# FillSensor.net
KiCad netlist of a schematic drawn in EAGLE
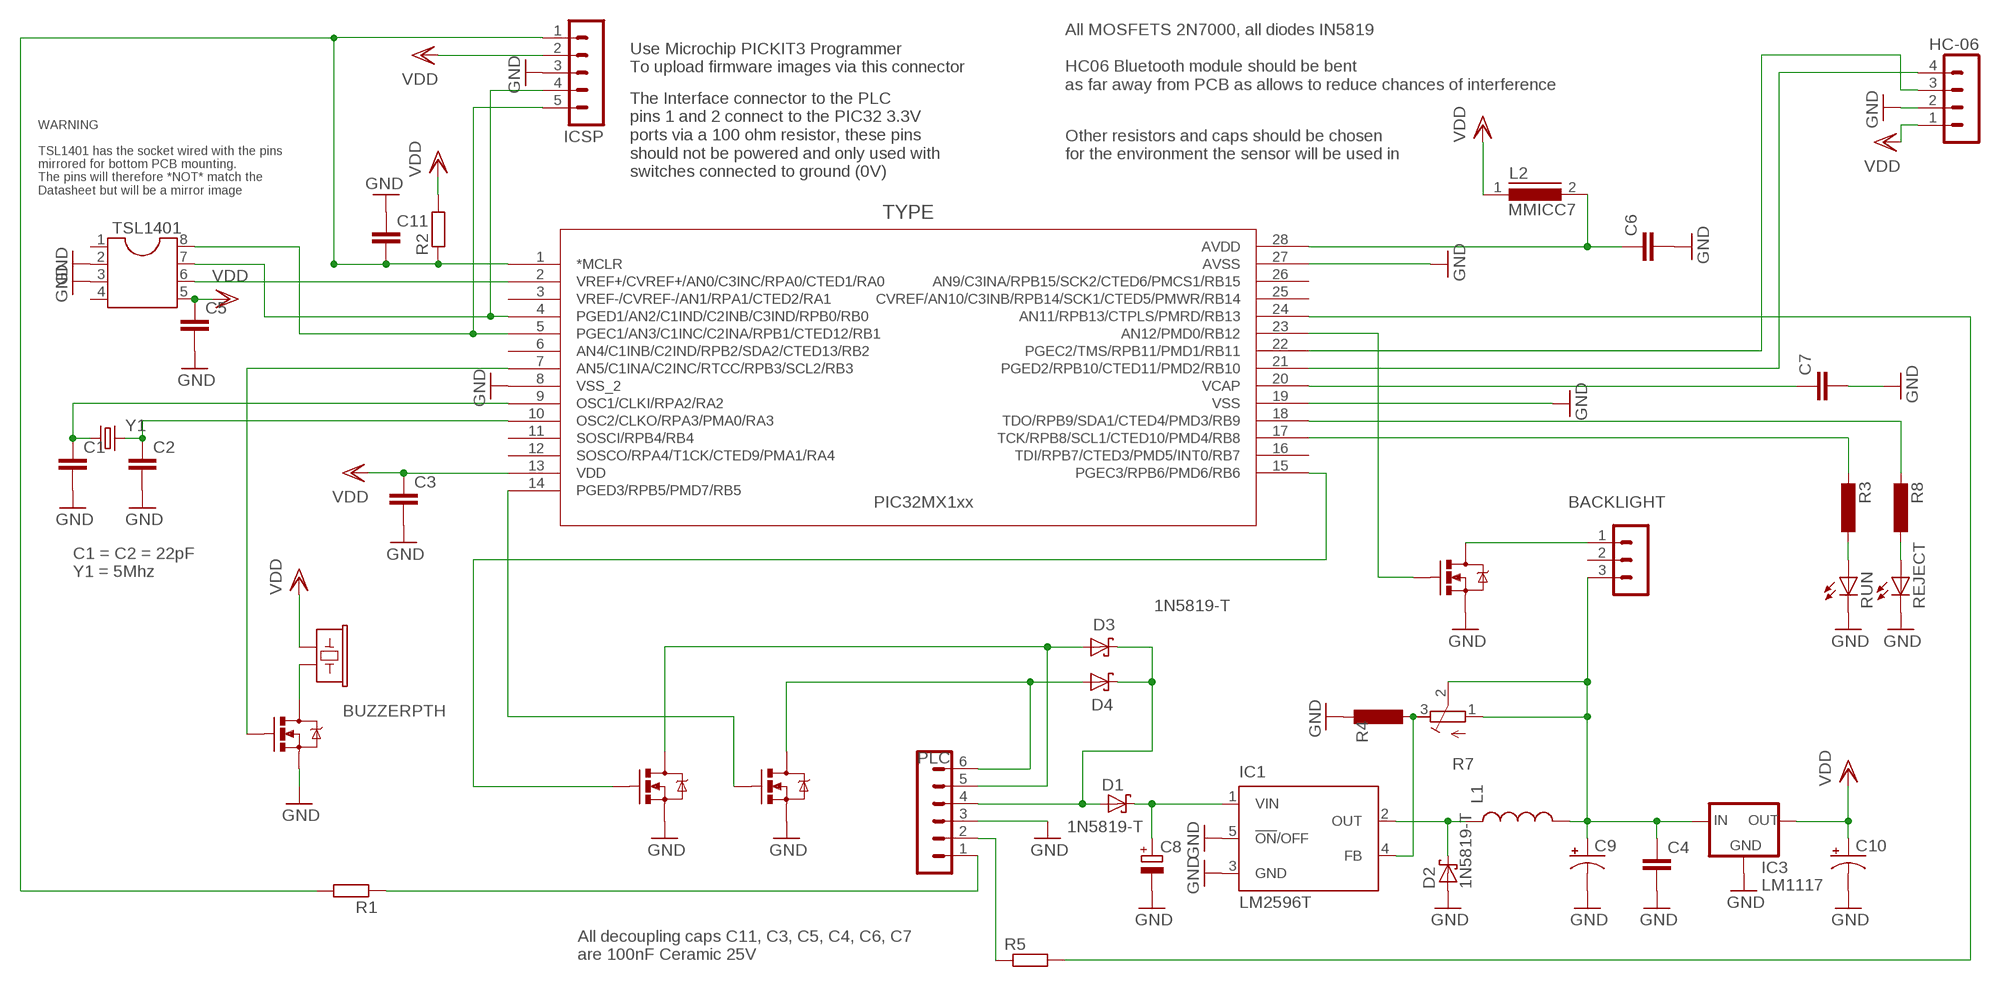
[diagram p0: schematic, sheet 1]

(export (version "E")
  (design (tool "Eeschema 10.0.6"))
  (components
    (comp (ref "BACKLIGHT")
      (value "MA03-1")
      (footprint "eagle-import:MA03-1")
      (libsource (lib "eagle-import") (part "MA03-1"))
    )
    (comp (ref "C1")
      (value "CAPPTH")
      (footprint "eagle-import:CAP-PTH-SMALL")
      (libsource (lib "eagle-import") (part "CAPPTH"))
    )
    (comp (ref "C2")
      (value "CAPPTH")
      (footprint "eagle-import:CAP-PTH-SMALL")
      (libsource (lib "eagle-import") (part "CAPPTH"))
    )
    (comp (ref "C3")
      (value "CAPPTH")
      (footprint "eagle-import:CAP-PTH-SMALL")
      (libsource (lib "eagle-import") (part "CAPPTH"))
    )
    (comp (ref "C4")
      (value "CAPPTH")
      (footprint "eagle-import:CAP-PTH-SMALL")
      (libsource (lib "eagle-import") (part "CAPPTH"))
    )
    (comp (ref "C5")
      (value "CAPPTH")
      (footprint "eagle-import:CAP-PTH-SMALL")
      (libsource (lib "eagle-import") (part "CAPPTH"))
    )
    (comp (ref "C6")
      (value "CAPPTH")
      (footprint "eagle-import:CAP-PTH-SMALL")
      (libsource (lib "eagle-import") (part "CAPPTH"))
    )
    (comp (ref "C7")
      (value "CAPPTH")
      (footprint "eagle-import:CAP-PTH-SMALL")
      (libsource (lib "eagle-import") (part "CAPPTH"))
    )
    (comp (ref "C8")
      (value "CPOL-EUE5-5")
      (footprint "eagle-import:E5-5")
      (libsource (lib "eagle-import") (part "CPOL-EUE5-5"))
    )
    (comp (ref "C9")
      (value "CAP_POLPTH2")
      (footprint "eagle-import:CPOL-RADIAL-10UF-25V")
      (libsource (lib "eagle-import") (part "CAP_POLPTH2"))
    )
    (comp (ref "C10")
      (value "CAP_POLPTH2")
      (footprint "eagle-import:CPOL-RADIAL-10UF-25V")
      (libsource (lib "eagle-import") (part "CAP_POLPTH2"))
    )
    (comp (ref "C11")
      (value "CAPPTH")
      (footprint "eagle-import:CAP-PTH-SMALL")
      (libsource (lib "eagle-import") (part "CAPPTH"))
    )
    (comp (ref "D1")
      (value "1N5819-T")
      (footprint "eagle-import:DO41-7.6")
      (libsource (lib "eagle-import") (part "1N5819-T"))
    )
    (comp (ref "D2")
      (value "1N5819-T")
      (footprint "eagle-import:DO41-7.6")
      (libsource (lib "eagle-import") (part "1N5819-T"))
    )
    (comp (ref "D3")
      (value "1N5819-T")
      (footprint "eagle-import:DO41-7.6")
      (libsource (lib "eagle-import") (part "1N5819-T"))
    )
    (comp (ref "D4")
      (value "1N5819-T")
      (footprint "eagle-import:DO41-7.6")
      (libsource (lib "eagle-import") (part "1N5819-T"))
    )
    (comp (ref "HC-06")
      (value "MA04-1")
      (footprint "eagle-import:MA04-1")
      (libsource (lib "eagle-import") (part "MA04-1"))
    )
    (comp (ref "IC1")
      (value "LM2596T")
      (footprint "eagle-import:T05D")
      (fields
        (field (name "MPN") "LM2596T-ADJ/LF02")
        (field (name "MPN_1") "LM2596T-ADJ/LF02")
        (field (name "OC_FARNELL") "9494162")
        (field (name "OC_NEWARK") "65K5910")
      )
      (libsource (lib "eagle-import") (part "LM2596T"))
    )
    (comp (ref "IC3")
      (value "LM1117")
      (footprint "eagle-import:TO252")
      (libsource (lib "eagle-import") (part "LM1117DTX-3.3"))
    )
    (comp (ref "ICSP")
      (value "MA05-1")
      (footprint "eagle-import:MA05-1")
      (libsource (lib "eagle-import") (part "MA05-1"))
    )
    (comp (ref "L1")
      (value "INDUCTORPWR")
      (footprint "eagle-import:CDRH125")
      (libsource (lib "eagle-import") (part "INDUCTORPWR"))
    )
    (comp (ref "L2")
      (value "MMICC7")
      (footprint "eagle-import:MMICC7")
      (libsource (lib "eagle-import") (part "MMICC7"))
    )
    (comp (ref "PLC")
      (value "MA06-1")
      (footprint "eagle-import:MA06-1")
      (libsource (lib "eagle-import") (part "MA06-1"))
    )
    (comp (ref "Q1")
      (value "MOSFET-NCHANNEL2N7000")
      (footprint "eagle-import:TO-92-AMMO")
      (libsource (lib "eagle-import") (part "MOSFET-NCHANNEL2N7000"))
    )
    (comp (ref "Q2")
      (value "MOSFET-NCHANNEL2N7000")
      (footprint "eagle-import:TO-92-AMMO")
      (libsource (lib "eagle-import") (part "MOSFET-NCHANNEL2N7000"))
    )
    (comp (ref "Q3")
      (value "MOSFET-NCHANNEL2N7000")
      (footprint "eagle-import:TO-92-AMMO")
      (libsource (lib "eagle-import") (part "MOSFET-NCHANNEL2N7000"))
    )
    (comp (ref "Q4")
      (value "MOSFET-NCHANNEL2N7000")
      (footprint "eagle-import:TO-92-AMMO")
      (libsource (lib "eagle-import") (part "MOSFET-NCHANNEL2N7000"))
    )
    (comp (ref "R1")
      (value "R-EU_0207/10")
      (footprint "eagle-import:0207_10")
      (libsource (lib "eagle-import") (part "R-EU_0207/10"))
    )
    (comp (ref "R2")
      (value "R-EU_0207/10")
      (footprint "eagle-import:0207_10")
      (libsource (lib "eagle-import") (part "R-EU_0207/10"))
    )
    (comp (ref "R3")
      (value "L-EU0207/10")
      (footprint "eagle-import:0207_10")
      (libsource (lib "eagle-import") (part "L-EU0207/10"))
    )
    (comp (ref "R4")
      (value "L-EU0207/10")
      (footprint "eagle-import:0207_10")
      (libsource (lib "eagle-import") (part "L-EU0207/10"))
    )
    (comp (ref "R5")
      (value "R-EU_0207/10")
      (footprint "eagle-import:0207_10")
      (libsource (lib "eagle-import") (part "R-EU_0207/10"))
    )
    (comp (ref "R7")
      (value "R-TRIMM64W")
      (footprint "eagle-import:RTRIM64W")
      (libsource (lib "eagle-import") (part "R-TRIMM64W"))
    )
    (comp (ref "R8")
      (value "L-EU0207/10")
      (footprint "eagle-import:0207_10")
      (libsource (lib "eagle-import") (part "L-EU0207/10"))
    )
    (comp (ref "REJECT")
      (value "LED5MM")
      (footprint "eagle-import:LED5MM")
      (libsource (lib "eagle-import") (part "LED5MM"))
    )
    (comp (ref "RUN")
      (value "LED5MM")
      (footprint "eagle-import:LED5MM")
      (libsource (lib "eagle-import") (part "LED5MM"))
    )
    (comp (ref "SG1")
      (value "BUZZERPTH")
      (footprint "eagle-import:BUZZER-12MM")
      (libsource (lib "eagle-import") (part "BUZZERPTH"))
    )
    (comp (ref "TSL1401")
      (value "DIL8")
      (footprint "eagle-import:DIL08")
      (libsource (lib "eagle-import") (part "DIL8"))
    )
    (comp (ref "U1")
      (value "PIC32MX150F128B-")
      (footprint "eagle-import:SPDIP28_300MC")
      (libsource (lib "eagle-import") (part "PIC32MX150F128B-"))
    )
    (comp (ref "Y1")
      (value "CRYSTALHC49UV")
      (footprint "eagle-import:HC49U-V")
      (libsource (lib "eagle-import") (part "CRYSTALHC49UV"))
    )
  )
  (nets
    (net (code "1") (name "GND") (class "Default")
      (node (ref "C1") (pin "2") (pinfunction "2_2") (pintype "passive"))
      (node (ref "C10") (pin "2") (pinfunction "-_2") (pintype "passive"))
      (node (ref "C11") (pin "1") (pinfunction "1_1") (pintype "passive"))
      (node (ref "C2") (pin "2") (pinfunction "2_2") (pintype "passive"))
      (node (ref "C3") (pin "2") (pinfunction "2_2") (pintype "passive"))
      (node (ref "C4") (pin "2") (pinfunction "2_2") (pintype "passive"))
      (node (ref "C5") (pin "2") (pinfunction "2_2") (pintype "passive"))
      (node (ref "C6") (pin "2") (pinfunction "2_2") (pintype "passive"))
      (node (ref "C7") (pin "2") (pinfunction "2_2") (pintype "passive"))
      (node (ref "C8") (pin "-") (pinfunction "-_-") (pintype "passive"))
      (node (ref "C9") (pin "2") (pinfunction "-_2") (pintype "passive"))
      (node (ref "D2") (pin "A") (pinfunction "A_A") (pintype "passive"))
      (node (ref "HC-06") (pin "2") (pinfunction "2_2") (pintype "passive"))
      (node (ref "IC1") (pin "3") (pinfunction "GND_3") (pintype "power_in"))
      (node (ref "IC1") (pin "5") (pinfunction "~{ON}/OFF_5") (pintype "input"))
      (node (ref "IC3") (pin "1") (pinfunction "GND_1") (pintype "input"))
      (node (ref "ICSP") (pin "3") (pinfunction "3_3") (pintype "passive"))
      (node (ref "PLC") (pin "3") (pinfunction "3_3") (pintype "passive"))
      (node (ref "Q1") (pin "1") (pinfunction "S_1") (pintype "passive"))
      (node (ref "Q2") (pin "1") (pinfunction "S_1") (pintype "passive"))
      (node (ref "Q3") (pin "1") (pinfunction "S_1") (pintype "passive"))
      (node (ref "Q4") (pin "1") (pinfunction "S_1") (pintype "passive"))
      (node (ref "R4") (pin "1") (pinfunction "1_1") (pintype "passive"))
      (node (ref "REJECT") (pin "K") (pinfunction "C_K") (pintype "passive"))
      (node (ref "RUN") (pin "K") (pinfunction "C_K") (pintype "passive"))
      (node (ref "TSL1401") (pin "2") (pinfunction "2_2") (pintype "passive"))
      (node (ref "TSL1401") (pin "3") (pinfunction "3_3") (pintype "passive"))
      (node (ref "U1") (pin "19") (pinfunction "VSS_19") (pintype "passive"))
      (node (ref "U1") (pin "27") (pinfunction "AVSS_27") (pintype "passive"))
      (node (ref "U1") (pin "8") (pinfunction "VSS_2_8") (pintype "passive"))
    )
    (net (code "2") (name "Net-(C9-+)") (class "Default")
      (node (ref "BACKLIGHT") (pin "3") (pinfunction "3_3") (pintype "passive"))
      (node (ref "C4") (pin "1") (pinfunction "1_1") (pintype "passive"))
      (node (ref "C9") (pin "1") (pinfunction "+_1") (pintype "passive"))
      (node (ref "IC3") (pin "2") (pinfunction "IN_2") (pintype "input"))
      (node (ref "L1") (pin "2") (pinfunction "2_2") (pintype "passive"))
      (node (ref "R7") (pin "1") (pinfunction "E_1") (pintype "passive"))
      (node (ref "R7") (pin "2") (pinfunction "S_2") (pintype "passive"))
    )
    (net (code "3") (name "Net-(D1-PadA)") (class "Default")
      (node (ref "D1") (pin "A") (pinfunction "A_A") (pintype "passive"))
      (node (ref "D3") (pin "C") (pinfunction "C_C") (pintype "passive"))
      (node (ref "D4") (pin "C") (pinfunction "C_C") (pintype "passive"))
      (node (ref "PLC") (pin "4") (pinfunction "4_4") (pintype "passive"))
    )
    (net (code "4") (name "Net-(IC1-FB)") (class "Default")
      (node (ref "IC1") (pin "4") (pinfunction "FB_4") (pintype "input"))
      (node (ref "R4") (pin "2") (pinfunction "2_2") (pintype "passive"))
      (node (ref "R7") (pin "3") (pinfunction "A_3") (pintype "passive"))
    )
    (net (code "5") (name "Net-(IC1-OUT)") (class "Default")
      (node (ref "D2") (pin "C") (pinfunction "C_C") (pintype "passive"))
      (node (ref "IC1") (pin "2") (pinfunction "OUT_2") (pintype "output"))
      (node (ref "L1") (pin "1") (pinfunction "1_1") (pintype "passive"))
    )
    (net (code "6") (name "Net-(IC1-VIN)") (class "Default")
      (node (ref "C8") (pin "+") (pinfunction "+_+") (pintype "passive"))
      (node (ref "D1") (pin "C") (pinfunction "C_C") (pintype "passive"))
      (node (ref "IC1") (pin "1") (pinfunction "VIN_1") (pintype "input"))
    )
    (net (code "7") (name "Net-(PLC-Pad1)") (class "Default")
      (node (ref "PLC") (pin "1") (pinfunction "1_1") (pintype "passive"))
      (node (ref "R1") (pin "1") (pinfunction "1_1") (pintype "passive"))
    )
    (net (code "8") (name "Net-(PLC-Pad2)") (class "Default")
      (node (ref "PLC") (pin "2") (pinfunction "2_2") (pintype "passive"))
      (node (ref "R5") (pin "1") (pinfunction "1_1") (pintype "passive"))
    )
    (net (code "9") (name "Net-(Q1-D)") (class "Default")
      (node (ref "D4") (pin "A") (pinfunction "A_A") (pintype "passive"))
      (node (ref "PLC") (pin "6") (pinfunction "6_6") (pintype "passive"))
      (node (ref "Q1") (pin "3") (pinfunction "D_3") (pintype "passive"))
    )
    (net (code "10") (name "Net-(Q1-G)") (class "Default")
      (node (ref "Q1") (pin "2") (pinfunction "G_2") (pintype "passive"))
      (node (ref "U1") (pin "14") (pinfunction "PGED3/RPB5/PMD7/RB5_14") (pintype "passive"))
    )
    (net (code "11") (name "Net-(Q2-D)") (class "Default")
      (node (ref "D3") (pin "A") (pinfunction "A_A") (pintype "passive"))
      (node (ref "PLC") (pin "5") (pinfunction "5_5") (pintype "passive"))
      (node (ref "Q2") (pin "3") (pinfunction "D_3") (pintype "passive"))
    )
    (net (code "12") (name "Net-(Q2-G)") (class "Default")
      (node (ref "Q2") (pin "2") (pinfunction "G_2") (pintype "passive"))
      (node (ref "U1") (pin "15") (pinfunction "PGEC3/RPB6/PMD6/RB6_15") (pintype "passive"))
    )
    (net (code "13") (name "Net-(Q3-D)") (class "Default")
      (node (ref "BACKLIGHT") (pin "1") (pinfunction "1_1") (pintype "passive"))
      (node (ref "Q3") (pin "3") (pinfunction "D_3") (pintype "passive"))
    )
    (net (code "14") (name "Net-(Q3-G)") (class "Default")
      (node (ref "Q3") (pin "2") (pinfunction "G_2") (pintype "passive"))
      (node (ref "U1") (pin "23") (pinfunction "AN12/PMD0/RB12_23") (pintype "passive"))
    )
    (net (code "15") (name "Net-(Q4-D)") (class "Default")
      (node (ref "Q4") (pin "3") (pinfunction "D_3") (pintype "passive"))
      (node (ref "SG1") (pin "-") (pinfunction "2_-") (pintype "passive"))
    )
    (net (code "16") (name "Net-(Q4-G)") (class "Default")
      (node (ref "Q4") (pin "2") (pinfunction "G_2") (pintype "passive"))
      (node (ref "U1") (pin "7") (pinfunction "AN5/C1INA/C2INC/RTCC/RPB3/SCL2/RB3_7") (pintype "passive"))
    )
    (net (code "17") (name "Net-(R3-Pad1)") (class "Default")
      (node (ref "R3") (pin "1") (pinfunction "1_1") (pintype "passive"))
      (node (ref "RUN") (pin "A") (pinfunction "A_A") (pintype "passive"))
    )
    (net (code "18") (name "Net-(R8-Pad1)") (class "Default")
      (node (ref "R8") (pin "1") (pinfunction "1_1") (pintype "passive"))
      (node (ref "REJECT") (pin "A") (pinfunction "A_A") (pintype "passive"))
    )
    (net (code "19") (name "Net-(U1-*MCLR)") (class "Default")
      (node (ref "C11") (pin "2") (pinfunction "2_2") (pintype "passive"))
      (node (ref "ICSP") (pin "1") (pinfunction "1_1") (pintype "passive"))
      (node (ref "R1") (pin "2") (pinfunction "2_2") (pintype "passive"))
      (node (ref "R2") (pin "1") (pinfunction "1_1") (pintype "passive"))
      (node (ref "U1") (pin "1") (pinfunction "*MCLR_1") (pintype "passive"))
    )
    (net (code "20") (name "Net-(U1-AN11{slash}RPB13{slash}CTPLS{slash}PMRD{slash}RB13)") (class "Default")
      (node (ref "R5") (pin "2") (pinfunction "2_2") (pintype "passive"))
      (node (ref "U1") (pin "24") (pinfunction "AN11/RPB13/CTPLS/PMRD/RB13_24") (pintype "passive"))
    )
    (net (code "21") (name "Net-(U1-AVDD)") (class "Default")
      (node (ref "C6") (pin "1") (pinfunction "1_1") (pintype "passive"))
      (node (ref "L2") (pin "2") (pinfunction "2_2") (pintype "passive"))
      (node (ref "U1") (pin "28") (pinfunction "AVDD_28") (pintype "passive"))
    )
    (net (code "22") (name "Net-(U1-OSC1{slash}CLKI{slash}RPA2{slash}RA2)") (class "Default")
      (node (ref "C1") (pin "1") (pinfunction "1_1") (pintype "passive"))
      (node (ref "U1") (pin "9") (pinfunction "OSC1/CLKI/RPA2/RA2_9") (pintype "passive"))
      (node (ref "Y1") (pin "1") (pinfunction "1_1") (pintype "passive"))
    )
    (net (code "23") (name "Net-(U1-OSC2{slash}CLKO{slash}RPA3{slash}PMA0{slash}RA3)") (class "Default")
      (node (ref "C2") (pin "1") (pinfunction "1_1") (pintype "passive"))
      (node (ref "U1") (pin "10") (pinfunction "OSC2/CLKO/RPA3/PMA0/RA3_10") (pintype "passive"))
      (node (ref "Y1") (pin "2") (pinfunction "2_2") (pintype "passive"))
    )
    (net (code "24") (name "Net-(U1-PGEC1{slash}AN3{slash}C1INC{slash}C2INA{slash}RPB1{slash}CTED12{slash}RB1)") (class "Default")
      (node (ref "ICSP") (pin "5") (pinfunction "5_5") (pintype "passive"))
      (node (ref "TSL1401") (pin "8") (pinfunction "8_8") (pintype "passive"))
      (node (ref "U1") (pin "5") (pinfunction "PGEC1/AN3/C1INC/C2INA/RPB1/CTED12/RB1_5") (pintype "passive"))
    )
    (net (code "25") (name "Net-(U1-PGEC2{slash}TMS{slash}RPB11{slash}PMD1{slash}RB11)") (class "Default")
      (node (ref "HC-06") (pin "3") (pinfunction "3_3") (pintype "passive"))
      (node (ref "U1") (pin "22") (pinfunction "PGEC2/TMS/RPB11/PMD1/RB11_22") (pintype "passive"))
    )
    (net (code "26") (name "Net-(U1-PGED1{slash}AN2{slash}C1IND{slash}C2INB{slash}C3IND{slash}RPB0{slash}RB0)") (class "Default")
      (node (ref "ICSP") (pin "4") (pinfunction "4_4") (pintype "passive"))
      (node (ref "TSL1401") (pin "7") (pinfunction "7_7") (pintype "passive"))
      (node (ref "U1") (pin "4") (pinfunction "PGED1/AN2/C1IND/C2INB/C3IND/RPB0/RB0_4") (pintype "passive"))
    )
    (net (code "27") (name "Net-(U1-PGED2{slash}RPB10{slash}CTED11{slash}PMD2{slash}RB10)") (class "Default")
      (node (ref "HC-06") (pin "4") (pinfunction "4_4") (pintype "passive"))
      (node (ref "U1") (pin "21") (pinfunction "PGED2/RPB10/CTED11/PMD2/RB10_21") (pintype "passive"))
    )
    (net (code "28") (name "Net-(U1-TCK{slash}RPB8{slash}SCL1{slash}CTED10{slash}PMD4{slash}RB8)") (class "Default")
      (node (ref "R3") (pin "2") (pinfunction "2_2") (pintype "passive"))
      (node (ref "U1") (pin "17") (pinfunction "TCK/RPB8/SCL1/CTED10/PMD4/RB8_17") (pintype "passive"))
    )
    (net (code "29") (name "Net-(U1-TDO{slash}RPB9{slash}SDA1{slash}CTED4{slash}PMD3{slash}RB9)") (class "Default")
      (node (ref "R8") (pin "2") (pinfunction "2_2") (pintype "passive"))
      (node (ref "U1") (pin "18") (pinfunction "TDO/RPB9/SDA1/CTED4/PMD3/RB9_18") (pintype "passive"))
    )
    (net (code "30") (name "Net-(U1-VCAP)") (class "Default")
      (node (ref "C7") (pin "1") (pinfunction "1_1") (pintype "passive"))
      (node (ref "U1") (pin "20") (pinfunction "VCAP_20") (pintype "passive"))
    )
    (net (code "31") (name "Net-(U1-VREF+{slash}CVREF+{slash}AN0{slash}C3INC{slash}RPA0{slash}CTED1{slash}RA0)") (class "Default")
      (node (ref "TSL1401") (pin "6") (pinfunction "6_6") (pintype "passive"))
      (node (ref "U1") (pin "2") (pinfunction "VREF+/CVREF+/AN0/C3INC/RPA0/CTED1/RA0_2") (pintype "passive"))
    )
    (net (code "32") (name "VDD") (class "Default")
      (node (ref "C10") (pin "1") (pinfunction "+_1") (pintype "passive"))
      (node (ref "C3") (pin "1") (pinfunction "1_1") (pintype "passive"))
      (node (ref "C5") (pin "1") (pinfunction "1_1") (pintype "passive"))
      (node (ref "HC-06") (pin "1") (pinfunction "1_1") (pintype "passive"))
      (node (ref "IC3") (pin "TAB") (pinfunction "OUT_TAB") (pintype "passive"))
      (node (ref "ICSP") (pin "2") (pinfunction "2_2") (pintype "passive"))
      (node (ref "L2") (pin "1") (pinfunction "1_1") (pintype "passive"))
      (node (ref "R2") (pin "2") (pinfunction "2_2") (pintype "passive"))
      (node (ref "SG1") (pin "+") (pinfunction "1_+") (pintype "passive"))
      (node (ref "TSL1401") (pin "5") (pinfunction "5_5") (pintype "passive"))
      (node (ref "U1") (pin "13") (pinfunction "VDD_13") (pintype "passive"))
    )
    (net (code "33") (name "unconnected-(BACKLIGHT-Pad2)") (class "Default")
      (node (ref "BACKLIGHT") (pin "2") (pinfunction "2_2") (pintype "passive"))
    )
    (net (code "34") (name "unconnected-(TSL1401-Pad1)") (class "Default")
      (node (ref "TSL1401") (pin "1") (pinfunction "1_1") (pintype "passive"))
    )
    (net (code "35") (name "unconnected-(TSL1401-Pad4)") (class "Default")
      (node (ref "TSL1401") (pin "4") (pinfunction "4_4") (pintype "passive"))
    )
    (net (code "36") (name "unconnected-(U1-AN4{slash}C1INB{slash}C2IND{slash}RPB2{slash}SDA2{slash}CTED13{slash}RB2-Pad6)") (class "Default")
      (node (ref "U1") (pin "6") (pinfunction "AN4/C1INB/C2IND/RPB2/SDA2/CTED13/RB2_6") (pintype "passive"))
    )
    (net (code "37") (name "unconnected-(U1-AN9{slash}C3INA{slash}RPB15{slash}SCK2{slash}CTED6{slash}PMCS1{slash}RB15-Pad26)") (class "Default")
      (node (ref "U1") (pin "26") (pinfunction "AN9/C3INA/RPB15/SCK2/CTED6/PMCS1/RB15_26") (pintype "passive"))
    )
    (net (code "38") (name "unconnected-(U1-CVREF{slash}AN10{slash}C3INB{slash}RPB14{slash}SCK1{slash}CTED5{slash}PMWR{slash}RB14-Pad25)") (class "Default")
      (node (ref "U1") (pin "25") (pinfunction "CVREF/AN10/C3INB/RPB14/SCK1/CTED5/PMWR/RB14_25") (pintype "passive"))
    )
    (net (code "39") (name "unconnected-(U1-SOSCI{slash}RPB4{slash}RB4-Pad11)") (class "Default")
      (node (ref "U1") (pin "11") (pinfunction "SOSCI/RPB4/RB4_11") (pintype "passive"))
    )
    (net (code "40") (name "unconnected-(U1-SOSCO{slash}RPA4{slash}T1CK{slash}CTED9{slash}PMA1{slash}RA4-Pad12)") (class "Default")
      (node (ref "U1") (pin "12") (pinfunction "SOSCO/RPA4/T1CK/CTED9/PMA1/RA4_12") (pintype "passive"))
    )
    (net (code "41") (name "unconnected-(U1-TDI{slash}RPB7{slash}CTED3{slash}PMD5{slash}INT0{slash}RB7-Pad16)") (class "Default")
      (node (ref "U1") (pin "16") (pinfunction "TDI/RPB7/CTED3/PMD5/INT0/RB7_16") (pintype "passive"))
    )
    (net (code "42") (name "unconnected-(U1-VREF-{slash}CVREF-{slash}AN1{slash}RPA1{slash}CTED2{slash}RA1-Pad3)") (class "Default")
      (node (ref "U1") (pin "3") (pinfunction "VREF-/CVREF-/AN1/RPA1/CTED2/RA1_3") (pintype "passive"))
    )
  )
)
